# Vis.net
KiCad netlist of a schematic drawn in EAGLE
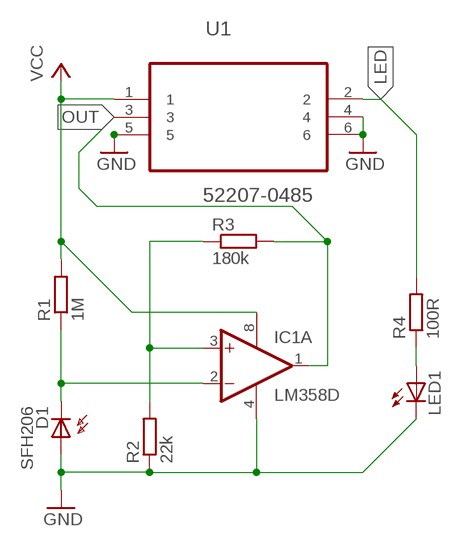
[diagram p0: schematic, sheet 1]

(export (version "E")
  (design (tool "Eeschema 10.0.6"))
  (components
    (comp (ref "D1")
      (value "SFH206")
      (footprint "eagle-import:SFH206")
      (fields (field (name "MPN") "SFH206K") (field (name "MF") "OSRAM"))
      (libsource (lib "eagle-import") (part "SFH206"))
    )
    (comp (ref "IC1")
      (value "LM358D")
      (footprint "eagle-import:SO08")
      (fields
        (field (name "MF") "TEXAS INSTRUMENTS")
        (field (name "MPN") "LM358DR")
        (field (name "OC_FARNELL") "1648685")
      )
      (libsource (lib "eagle-import") (part "LM358D"))
    )
    (comp (ref "LED1")
      (value "LED5MM")
      (footprint "eagle-import:LED5MM")
      (fields (field (name "MF") "WURTH ELEKTRONIK") (field (name "MPN") "151053GS03000"))
      (libsource (lib "eagle-import") (part "LED5MM"))
    )
    (comp (ref "R1")
      (value "1M")
      (footprint "eagle-import:R1206")
      (libsource (lib "eagle-import") (part "R-EU_R1206"))
    )
    (comp (ref "R2")
      (value "22k")
      (footprint "eagle-import:R1206")
      (libsource (lib "eagle-import") (part "R-EU_R1206"))
    )
    (comp (ref "R3")
      (value "180k")
      (footprint "eagle-import:R1206")
      (fields (field (name "MF") "TE CONNECTIVITY") (field (name "MPN") "CRGH1206F180K"))
      (libsource (lib "eagle-import") (part "R-EU_R1206"))
    )
    (comp (ref "R4")
      (value "100R")
      (footprint "eagle-import:R1206")
      (libsource (lib "eagle-import") (part "R-EU_R1206"))
    )
    (comp (ref "U1")
      (value "52207-0485")
      (footprint "eagle-import:MOLEX_52207-0485")
      (libsource (lib "eagle-import") (part "52207-0485"))
    )
  )
  (nets
    (net (code "1") (name "GND") (class "Default")
      (node (ref "D1") (pin "A") (pinfunction "A_A") (pintype "passive"))
      (node (ref "IC1") (pin "4") (pinfunction "V-_4") (pintype "power_in"))
      (node (ref "LED1") (pin "K") (pinfunction "C_K") (pintype "passive"))
      (node (ref "R2") (pin "1") (pinfunction "1_1") (pintype "passive"))
      (node (ref "U1") (pin "4") (pinfunction "4_4") (pintype "passive"))
      (node (ref "U1") (pin "5") (pinfunction "5_5") (pintype "passive"))
      (node (ref "U1") (pin "6") (pinfunction "6_6") (pintype "passive"))
    )
    (net (code "2") (name "LED") (class "Default")
      (node (ref "R4") (pin "2") (pinfunction "2_2") (pintype "passive"))
      (node (ref "U1") (pin "2") (pinfunction "2_2") (pintype "passive"))
    )
    (net (code "3") (name "Net-(D1-C)") (class "Default")
      (node (ref "D1") (pin "K") (pinfunction "C_K") (pintype "passive"))
      (node (ref "IC1") (pin "2") (pinfunction "-IN_2") (pintype "input"))
      (node (ref "R1") (pin "1") (pinfunction "1_1") (pintype "passive"))
    )
    (net (code "4") (name "Net-(IC1A-+IN)") (class "Default")
      (node (ref "IC1") (pin "3") (pinfunction "+IN_3") (pintype "input"))
      (node (ref "R2") (pin "2") (pinfunction "2_2") (pintype "passive"))
      (node (ref "R3") (pin "1") (pinfunction "1_1") (pintype "passive"))
    )
    (net (code "5") (name "Net-(LED1-PadA)") (class "Default")
      (node (ref "LED1") (pin "A") (pinfunction "A_A") (pintype "passive"))
      (node (ref "R4") (pin "1") (pinfunction "1_1") (pintype "passive"))
    )
    (net (code "6") (name "OUT") (class "Default")
      (node (ref "IC1") (pin "1") (pinfunction "OUT_1") (pintype "output"))
      (node (ref "R3") (pin "2") (pinfunction "2_2") (pintype "passive"))
      (node (ref "U1") (pin "3") (pinfunction "3_3") (pintype "passive"))
    )
    (net (code "7") (name "VCC") (class "Default")
      (node (ref "IC1") (pin "8") (pinfunction "V+_8") (pintype "power_in"))
      (node (ref "R1") (pin "2") (pinfunction "2_2") (pintype "passive"))
      (node (ref "U1") (pin "1") (pinfunction "1_1") (pintype "passive"))
    )
  )
)
